# RightEar.net
KiCad netlist of a schematic drawn in Altium Designer
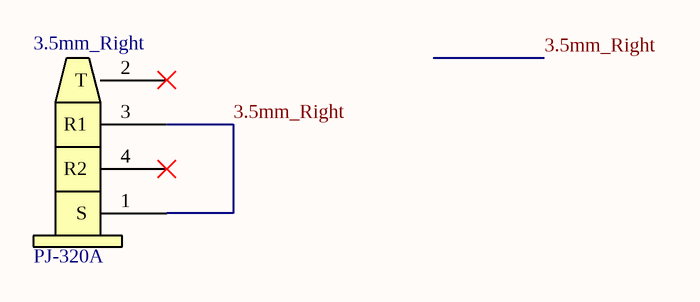
[diagram p0: RightEar.SchDoc]

(export (version "E")
  (design (tool "Eeschema 10.0.6"))
  (components
    (comp (ref "3.5mm_Right")
      (value "PJ-320A")
      (footprint "PCBComponent_1")
      (description "A thru hole 3.5mm TRRS audio jack connector")
      (libsource (lib "PJ-320A-New") (part "PJ-320A"))
    )
  )
  (nets
    (net (code "1") (name "/3.5mm_Right") (class "Default")
      (node (ref "3.5mm_Right") (pin "1") (pinfunction "S_1") (pintype "passive"))
      (node (ref "3.5mm_Right") (pin "3") (pinfunction "R1_3") (pintype "passive"))
    )
    (net (code "2") (name "unconnected-(3.5mm_Right-R2-Pad4)") (class "Default")
      (node (ref "3.5mm_Right") (pin "4") (pinfunction "R2_4") (pintype "passive+no_connect"))
    )
    (net (code "3") (name "unconnected-(3.5mm_Right-T-Pad2)") (class "Default")
      (node (ref "3.5mm_Right") (pin "2") (pinfunction "T_2") (pintype "passive+no_connect"))
    )
  )
)
